# AD9833.net
KiCad netlist of a schematic drawn in Altium Designer
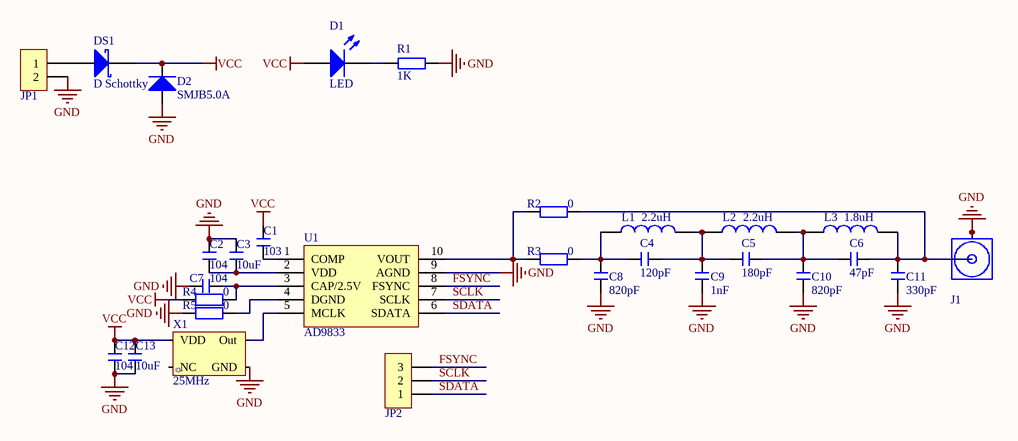
[diagram p0: AD9833.SchDoc]

(export (version "E")
  (design (tool "Eeschema 10.0.6"))
  (components
    (comp (ref "C1")
      (value "103")
      (footprint "C 0603")
      (description "无极性贴片电容")
      (fields (field (name "版权归属") "源创客"))
      (libsource (lib "电阻-电容-电感") (part "C"))
    )
    (comp (ref "C2")
      (value "104")
      (footprint "C 0603")
      (description "无极性贴片电容")
      (fields (field (name "版权归属") "源创客"))
      (libsource (lib "电阻-电容-电感") (part "C"))
    )
    (comp (ref "C3")
      (value "10uF")
      (footprint "C 0603")
      (description "无极性贴片电容")
      (fields (field (name "版权归属") "源创客"))
      (libsource (lib "电阻-电容-电感") (part "C"))
    )
    (comp (ref "C4")
      (value "120pF")
      (footprint "C 0603")
      (description "无极性贴片电容")
      (fields (field (name "版权归属") "源创客"))
      (libsource (lib "电阻-电容-电感") (part "C"))
    )
    (comp (ref "C5")
      (value "180pF")
      (footprint "C 0603")
      (description "无极性贴片电容")
      (fields (field (name "版权归属") "源创客"))
      (libsource (lib "电阻-电容-电感") (part "C"))
    )
    (comp (ref "C6")
      (value "47pF")
      (footprint "C 0603")
      (description "无极性贴片电容")
      (fields (field (name "版权归属") "源创客"))
      (libsource (lib "电阻-电容-电感") (part "C"))
    )
    (comp (ref "C7")
      (value "104")
      (footprint "C 0603")
      (description "无极性贴片电容")
      (fields (field (name "版权归属") "源创客"))
      (libsource (lib "电阻-电容-电感") (part "C"))
    )
    (comp (ref "C8")
      (value "820pF")
      (footprint "C 0603")
      (description "无极性贴片电容")
      (fields (field (name "版权归属") "源创客"))
      (libsource (lib "电阻-电容-电感") (part "C"))
    )
    (comp (ref "C9")
      (value "1nF")
      (footprint "C 0603")
      (description "无极性贴片电容")
      (fields (field (name "版权归属") "源创客"))
      (libsource (lib "电阻-电容-电感") (part "C"))
    )
    (comp (ref "C10")
      (value "820pF")
      (footprint "C 0603")
      (description "无极性贴片电容")
      (fields (field (name "版权归属") "源创客"))
      (libsource (lib "电阻-电容-电感") (part "C"))
    )
    (comp (ref "C11")
      (value "330pF")
      (footprint "C 0603")
      (description "无极性贴片电容")
      (fields (field (name "版权归属") "源创客"))
      (libsource (lib "电阻-电容-电感") (part "C"))
    )
    (comp (ref "C12")
      (value "104")
      (footprint "C 0603")
      (description "无极性贴片电容")
      (fields (field (name "版权归属") "源创客"))
      (libsource (lib "电阻-电容-电感") (part "C"))
    )
    (comp (ref "C13")
      (value "10uF")
      (footprint "C 0603")
      (description "无极性贴片电容")
      (fields (field (name "版权归属") "源创客"))
      (libsource (lib "电阻-电容-电感") (part "C"))
    )
    (comp (ref "D1")
      (value "LED")
      (footprint "LED_0805")
      (description "发光二极管")
      (fields (field (name "PUBLISHER") "Altium Limited"))
      (libsource (lib "LIB") (part "LED"))
    )
    (comp (ref "D2")
      (value "TVS")
      (footprint "DIODE-SMA")
      (description "TVS保护")
      (fields (field (name "TYPE") "SMJB5.0A") (field (name "PUBLISHER") "Altium Limited"))
      (libsource (lib "LIB") (part "TVS"))
    )
    (comp (ref "DS1")
      (value "D Schottky")
      (footprint "DIODE-SMA")
      (description "Schottky Diode")
      (fields (field (name "PUBLISHER") "Altium Limited"))
      (libsource (lib "LIB") (part "D Schottky"))
    )
    (comp (ref "J1") (value "COAX") (footprint "MCX5.08-5-H") (libsource (lib "LIB") (part "COAX")))
    (comp (ref "JP1")
      (value "HDR-1X2")
      (footprint "XH2.54-2P_H")
      (description "2P接插件")
      (fields (field (name "版权归属") "源创客"))
      (libsource (lib "接插件") (part "Header 2"))
    )
    (comp (ref "JP2")
      (value "HDR-1X3")
      (footprint "HDR-1X3_H")
      (description "3P接插件")
      (fields (field (name "版权归属") "源创客"))
      (libsource (lib "接插件") (part "Header 3"))
    )
    (comp (ref "L1")
      (value "2.2uH")
      (footprint "L 0603")
      (description "小功率贴片电感")
      (fields (field (name "版权归属") "源创客"))
      (libsource (lib "电阻-电容-电感") (part "L"))
    )
    (comp (ref "L2")
      (value "2.2uH")
      (footprint "L 0603")
      (description "小功率贴片电感")
      (fields (field (name "版权归属") "源创客"))
      (libsource (lib "电阻-电容-电感") (part "L"))
    )
    (comp (ref "L3")
      (value "1.8uH")
      (footprint "L 0603")
      (description "小功率贴片电感")
      (fields (field (name "版权归属") "源创客"))
      (libsource (lib "电阻-电容-电感") (part "L"))
    )
    (comp (ref "R1")
      (value "1K")
      (footprint "R 0603")
      (description "贴片电阻")
      (fields (field (name "版权归属") "源创客"))
      (libsource (lib "电阻-电容-电感") (part "R"))
    )
    (comp (ref "R2")
      (value "0")
      (footprint "R 0603")
      (description "贴片电阻")
      (fields (field (name "版权归属") "源创客"))
      (libsource (lib "电阻-电容-电感") (part "R"))
    )
    (comp (ref "R3")
      (value "0")
      (footprint "R 0603")
      (description "贴片电阻")
      (fields (field (name "版权归属") "源创客"))
      (libsource (lib "电阻-电容-电感") (part "R"))
    )
    (comp (ref "R4")
      (value "0")
      (footprint "R 0603")
      (description "贴片电阻")
      (fields (field (name "版权归属") "源创客"))
      (libsource (lib "电阻-电容-电感") (part "R"))
    )
    (comp (ref "R5")
      (value "0")
      (footprint "R 0603")
      (description "贴片电阻")
      (fields (field (name "版权归属") "源创客"))
      (libsource (lib "电阻-电容-电感") (part "R"))
    )
    (comp (ref "U1")
      (value "AD9833")
      (footprint "MSOP-UN10_N")
      (description "低功耗、12.75mW、2.3V至5.5V可编程波形发生器")
      (libsource (lib "LIB") (part "AD9833"))
    )
    (comp (ref "X1")
      (value "XTAL")
      (footprint "XTAL-3225")
      (description "有源晶振")
      (fields (field (name "FREQUENCY") "25MHz"))
      (libsource (lib "LIB") (part "XTAL_Oscillator"))
    )
  )
  (nets
    (net (code "1") (name "/FSYNC") (class "Default")
      (node (ref "JP2") (pin "3") (pinfunction "3_3") (pintype "passive"))
      (node (ref "U1") (pin "8") (pinfunction "FSYNC_8") (pintype "passive"))
    )
    (net (code "2") (name "/SCLK") (class "Default")
      (node (ref "JP2") (pin "2") (pinfunction "2_2") (pintype "passive"))
      (node (ref "U1") (pin "7") (pinfunction "SCLK_7") (pintype "passive"))
    )
    (net (code "3") (name "/SDATA") (class "Default")
      (node (ref "JP2") (pin "1") (pinfunction "1_1") (pintype "passive"))
      (node (ref "U1") (pin "6") (pinfunction "SDATA_6") (pintype "passive"))
    )
    (net (code "4") (name "GND") (class "Default")
      (node (ref "C10") (pin "1") (pinfunction "1_1") (pintype "passive"))
      (node (ref "C11") (pin "2") (pinfunction "2_2") (pintype "passive"))
      (node (ref "C12") (pin "2") (pinfunction "2_2") (pintype "passive"))
      (node (ref "C13") (pin "1") (pinfunction "1_1") (pintype "passive"))
      (node (ref "C2") (pin "1") (pinfunction "1_1") (pintype "passive"))
      (node (ref "C3") (pin "2") (pinfunction "2_2") (pintype "passive"))
      (node (ref "C7") (pin "2") (pinfunction "2_2") (pintype "passive"))
      (node (ref "C8") (pin "1") (pinfunction "1_1") (pintype "passive"))
      (node (ref "C9") (pin "2") (pinfunction "2_2") (pintype "passive"))
      (node (ref "D2") (pin "1") (pinfunction "A_1") (pintype "passive"))
      (node (ref "J1") (pin "2") (pinfunction "GND_2") (pintype "passive"))
      (node (ref "J1") (pin "3") (pinfunction "GND_3") (pintype "passive"))
      (node (ref "J1") (pin "4") (pinfunction "GND_4") (pintype "passive"))
      (node (ref "J1") (pin "5") (pinfunction "GND_5") (pintype "passive"))
      (node (ref "JP1") (pin "2") (pinfunction "2_2") (pintype "passive"))
      (node (ref "R1") (pin "2") (pinfunction "2_2") (pintype "passive"))
      (node (ref "R5") (pin "1") (pinfunction "1_1") (pintype "passive"))
      (node (ref "U1") (pin "9") (pinfunction "AGND_9") (pintype "passive"))
      (node (ref "X1") (pin "2") (pinfunction "GND_2") (pintype "passive"))
    )
    (net (code "5") (name "Net-(C4-Pad1)") (class "Default")
      (node (ref "C4") (pin "1") (pinfunction "1_1") (pintype "passive"))
      (node (ref "C5") (pin "1") (pinfunction "1_1") (pintype "passive"))
      (node (ref "C9") (pin "1") (pinfunction "1_1") (pintype "passive"))
      (node (ref "L1") (pin "2") (pinfunction "2_2") (pintype "passive"))
      (node (ref "L2") (pin "1") (pinfunction "1_1") (pintype "passive"))
    )
    (net (code "6") (name "Net-(C4-Pad2)") (class "Default")
      (node (ref "C4") (pin "2") (pinfunction "2_2") (pintype "passive"))
      (node (ref "C8") (pin "2") (pinfunction "2_2") (pintype "passive"))
      (node (ref "L1") (pin "1") (pinfunction "1_1") (pintype "passive"))
      (node (ref "R3") (pin "2") (pinfunction "2_2") (pintype "passive"))
    )
    (net (code "7") (name "Net-(C10-Pad2)") (class "Default")
      (node (ref "C10") (pin "2") (pinfunction "2_2") (pintype "passive"))
      (node (ref "C5") (pin "2") (pinfunction "2_2") (pintype "passive"))
      (node (ref "C6") (pin "2") (pinfunction "2_2") (pintype "passive"))
      (node (ref "L2") (pin "2") (pinfunction "2_2") (pintype "passive"))
      (node (ref "L3") (pin "1") (pinfunction "1_1") (pintype "passive"))
    )
    (net (code "8") (name "Net-(D1-K)") (class "Default")
      (node (ref "D1") (pin "2") (pinfunction "K_2") (pintype "passive"))
      (node (ref "R1") (pin "1") (pinfunction "1_1") (pintype "passive"))
    )
    (net (code "9") (name "Net-(DS1-Pad1)") (class "Default")
      (node (ref "DS1") (pin "1") (pinfunction "1_1") (pintype "passive"))
      (node (ref "JP1") (pin "1") (pinfunction "1_1") (pintype "passive"))
    )
    (net (code "10") (name "Net-(J1-Signal)") (class "Default")
      (node (ref "C11") (pin "1") (pinfunction "1_1") (pintype "passive"))
      (node (ref "C6") (pin "1") (pinfunction "1_1") (pintype "passive"))
      (node (ref "J1") (pin "1") (pinfunction "Signal_1") (pintype "passive"))
      (node (ref "L3") (pin "2") (pinfunction "2_2") (pintype "passive"))
      (node (ref "R2") (pin "2") (pinfunction "2_2") (pintype "passive"))
    )
    (net (code "11") (name "Net-(U1-CAP{slash}2.5V)") (class "Default")
      (node (ref "C7") (pin "1") (pinfunction "1_1") (pintype "passive"))
      (node (ref "R4") (pin "2") (pinfunction "2_2") (pintype "passive"))
      (node (ref "U1") (pin "3") (pinfunction "CAP/2.5V_3") (pintype "passive"))
    )
    (net (code "12") (name "Net-(U1-COMP)") (class "Default")
      (node (ref "C1") (pin "2") (pinfunction "2_2") (pintype "passive"))
      (node (ref "U1") (pin "1") (pinfunction "COMP_1") (pintype "passive"))
    )
    (net (code "13") (name "Net-(U1-DGND)") (class "Default")
      (node (ref "R5") (pin "2") (pinfunction "2_2") (pintype "passive"))
      (node (ref "U1") (pin "4") (pinfunction "DGND_4") (pintype "passive"))
    )
    (net (code "14") (name "Net-(U1-MCLK)") (class "Default")
      (node (ref "U1") (pin "5") (pinfunction "MCLK_5") (pintype "passive"))
      (node (ref "X1") (pin "3") (pinfunction "Out_3") (pintype "passive"))
    )
    (net (code "15") (name "Net-(U1-VDD)") (class "Default")
      (node (ref "C2") (pin "2") (pinfunction "2_2") (pintype "passive"))
      (node (ref "C3") (pin "1") (pinfunction "1_1") (pintype "passive"))
      (node (ref "U1") (pin "2") (pinfunction "VDD_2") (pintype "passive"))
    )
    (net (code "16") (name "Net-(U1-VOUT)") (class "Default")
      (node (ref "R2") (pin "1") (pinfunction "1_1") (pintype "passive"))
      (node (ref "R3") (pin "1") (pinfunction "1_1") (pintype "passive"))
      (node (ref "U1") (pin "10") (pinfunction "VOUT_10") (pintype "passive"))
    )
    (net (code "17") (name "VCC") (class "Default")
      (node (ref "C1") (pin "1") (pinfunction "1_1") (pintype "passive"))
      (node (ref "C12") (pin "1") (pinfunction "1_1") (pintype "passive"))
      (node (ref "C13") (pin "2") (pinfunction "2_2") (pintype "passive"))
      (node (ref "D1") (pin "1") (pinfunction "A_1") (pintype "passive"))
      (node (ref "D2") (pin "2") (pinfunction "K_2") (pintype "passive"))
      (node (ref "DS1") (pin "2") (pinfunction "2_2") (pintype "passive"))
      (node (ref "R4") (pin "1") (pinfunction "1_1") (pintype "passive"))
      (node (ref "X1") (pin "4") (pinfunction "VDD_4") (pintype "passive"))
    )
    (net (code "18") (name "unconnected-(X1-NC-Pad1)") (class "Default")
      (node (ref "X1") (pin "1") (pinfunction "NC_1") (pintype "passive"))
    )
  )
)
